# list_1.net
KiCad netlist of a schematic drawn in EAGLE
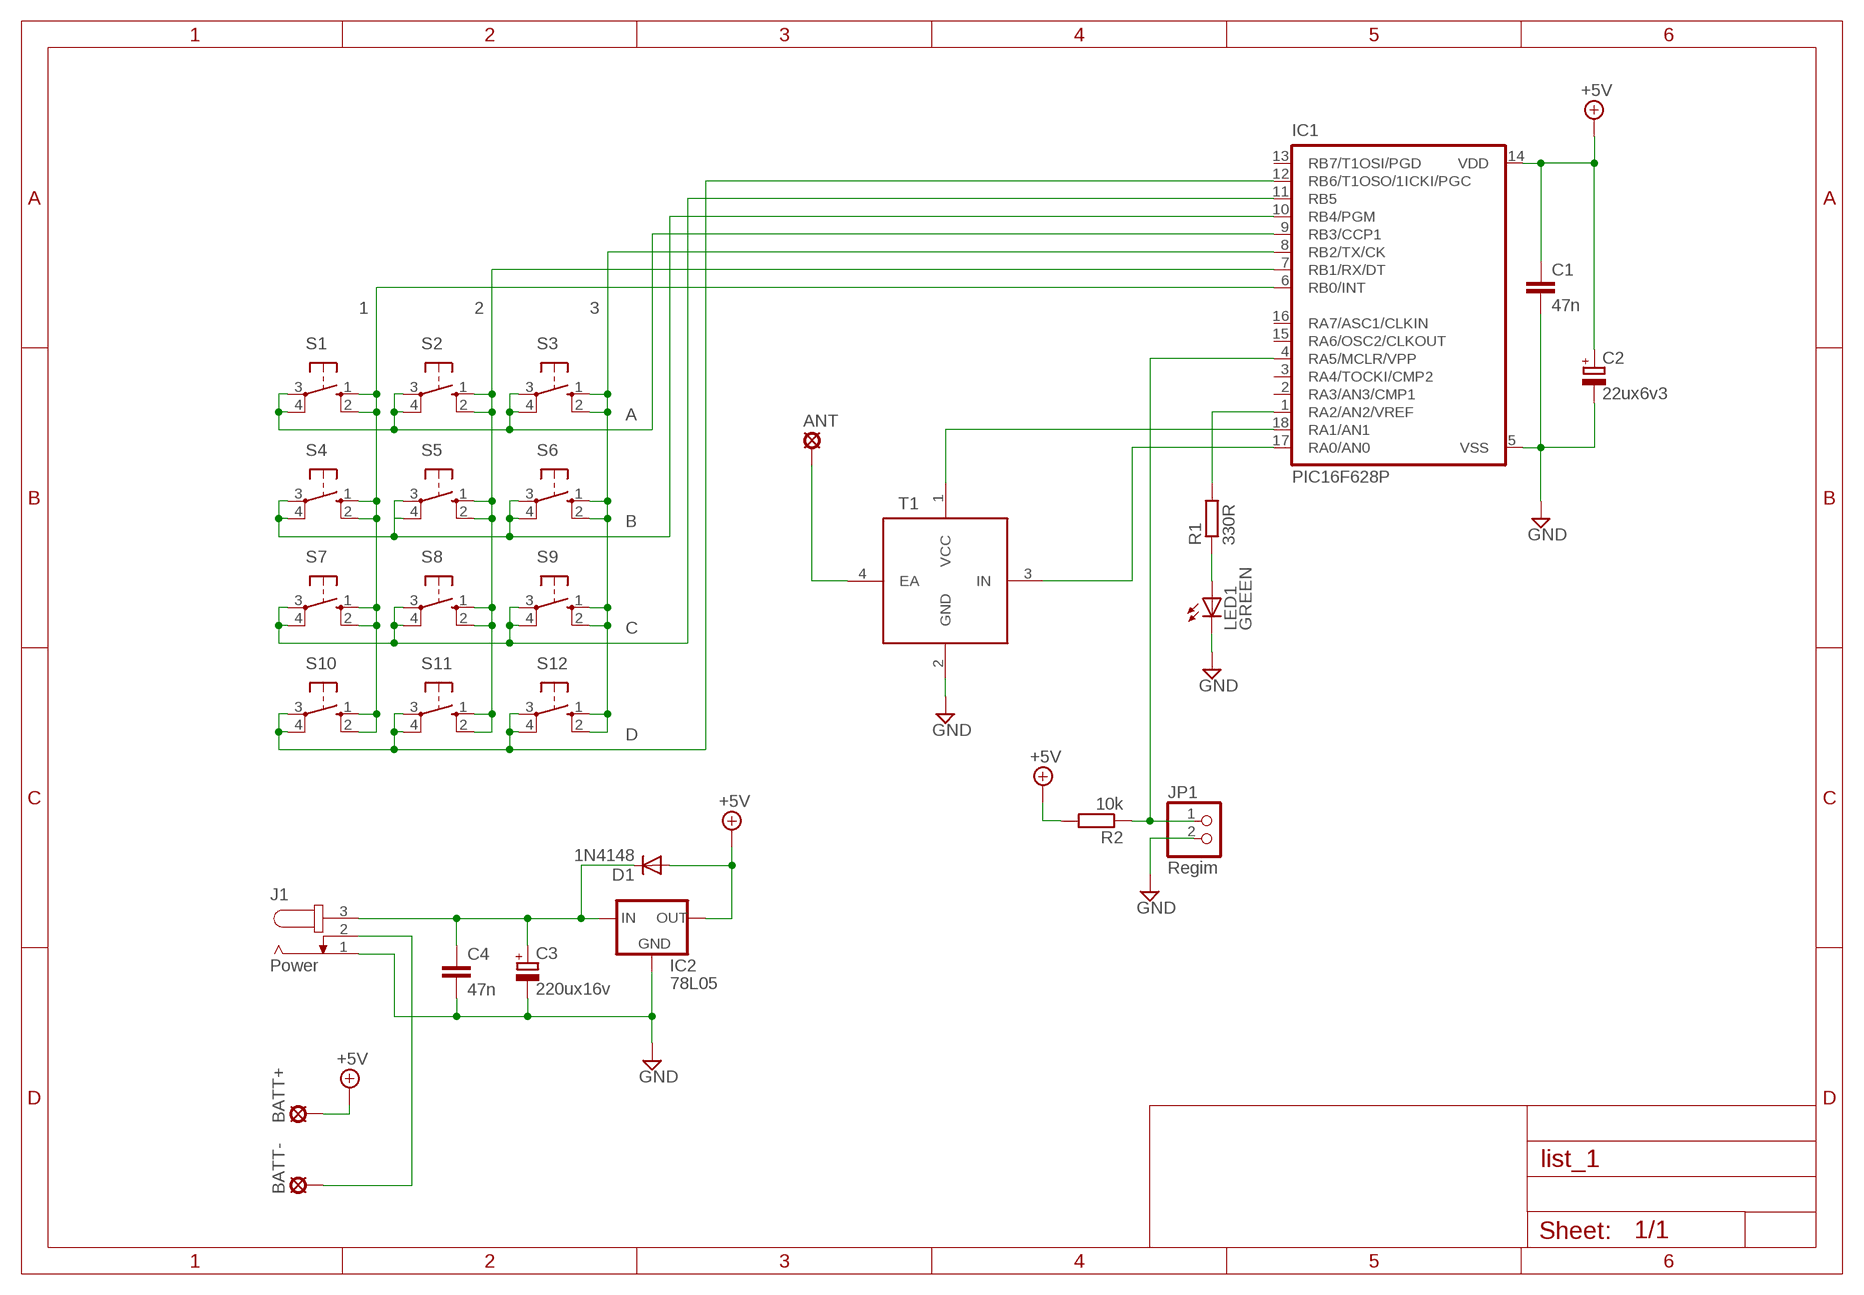
[diagram p0: schematic, sheet 1]

(export (version "E")
  (design (tool "Eeschema 10.0.6"))
  (components
    (comp (ref "ANT")
      (value "SE11")
      (footprint "eagle-import:SE11")
      (libsource (lib "eagle-import") (part "SE11"))
    )
    (comp (ref "BATT+")
      (value "SE11")
      (footprint "eagle-import:SE11")
      (libsource (lib "eagle-import") (part "SE11"))
    )
    (comp (ref "BATT-")
      (value "SE11")
      (footprint "eagle-import:SE11")
      (libsource (lib "eagle-import") (part "SE11"))
    )
    (comp (ref "C1")
      (value "47n")
      (footprint "eagle-import:C050-025X075")
      (libsource (lib "eagle-import") (part "C-EU050-025X075"))
    )
    (comp (ref "C2")
      (value "22ux6v3")
      (footprint "eagle-import:E2,5-5")
      (libsource (lib "eagle-import") (part "CPOL-EUE2.5-5"))
    )
    (comp (ref "C3")
      (value "220ux16v")
      (footprint "eagle-import:E2,5-5")
      (libsource (lib "eagle-import") (part "CPOL-EUE2.5-5"))
    )
    (comp (ref "C4")
      (value "47n")
      (footprint "eagle-import:C050-025X075")
      (libsource (lib "eagle-import") (part "C-EU050-025X075"))
    )
    (comp (ref "D1")
      (value "1N4148")
      (footprint "eagle-import:DO35-7")
      (libsource (lib "eagle-import") (part "1N4148DO35-7"))
    )
    (comp (ref "IC1")
      (value "PIC16F628P")
      (footprint "eagle-import:DIL18")
      (libsource (lib "eagle-import") (part "PIC16F628P"))
    )
    (comp (ref "IC2")
      (value "78L05")
      (footprint "eagle-import:78LXX")
      (libsource (lib "eagle-import") (part "78LXX"))
    )
    (comp (ref "J1")
      (value "Power")
      (footprint "eagle-import:SPC4077")
      (libsource (lib "eagle-import") (part "JACK-PLUG0"))
    )
    (comp (ref "JP1")
      (value "Regim")
      (footprint "eagle-import:1X02")
      (libsource (lib "eagle-import") (part "PINHD-1X2"))
    )
    (comp (ref "LED1")
      (value "GREEN")
      (footprint "eagle-import:LED3MM")
      (libsource (lib "eagle-import") (part "LED3MM"))
    )
    (comp (ref "R1")
      (value "330R")
      (footprint "eagle-import:0207_10")
      (libsource (lib "eagle-import") (part "R-EU_0207/10"))
    )
    (comp (ref "R2")
      (value "10k")
      (footprint "eagle-import:0207_10")
      (libsource (lib "eagle-import") (part "R-EU_0207/10"))
    )
    (comp (ref "S1")
      (value "40-XX")
      (footprint "eagle-import:B3F-40XX")
      (libsource (lib "eagle-import") (part "40-XX"))
    )
    (comp (ref "S2")
      (value "40-XX")
      (footprint "eagle-import:B3F-40XX")
      (libsource (lib "eagle-import") (part "40-XX"))
    )
    (comp (ref "S3")
      (value "40-XX")
      (footprint "eagle-import:B3F-40XX")
      (libsource (lib "eagle-import") (part "40-XX"))
    )
    (comp (ref "S4")
      (value "40-XX")
      (footprint "eagle-import:B3F-40XX")
      (libsource (lib "eagle-import") (part "40-XX"))
    )
    (comp (ref "S5")
      (value "40-XX")
      (footprint "eagle-import:B3F-40XX")
      (libsource (lib "eagle-import") (part "40-XX"))
    )
    (comp (ref "S6")
      (value "40-XX")
      (footprint "eagle-import:B3F-40XX")
      (libsource (lib "eagle-import") (part "40-XX"))
    )
    (comp (ref "S7")
      (value "40-XX")
      (footprint "eagle-import:B3F-40XX")
      (libsource (lib "eagle-import") (part "40-XX"))
    )
    (comp (ref "S8")
      (value "40-XX")
      (footprint "eagle-import:B3F-40XX")
      (libsource (lib "eagle-import") (part "40-XX"))
    )
    (comp (ref "S9")
      (value "40-XX")
      (footprint "eagle-import:B3F-40XX")
      (libsource (lib "eagle-import") (part "40-XX"))
    )
    (comp (ref "S10")
      (value "40-XX")
      (footprint "eagle-import:B3F-40XX")
      (libsource (lib "eagle-import") (part "40-XX"))
    )
    (comp (ref "S11")
      (value "40-XX")
      (footprint "eagle-import:B3F-40XX")
      (libsource (lib "eagle-import") (part "40-XX"))
    )
    (comp (ref "S12")
      (value "40-XX")
      (footprint "eagle-import:B3F-40XX")
      (libsource (lib "eagle-import") (part "40-XX"))
    )
    (comp (ref "T1")
      (value "RT4")
      (footprint "eagle-import:RT4")
      (libsource (lib "eagle-import") (part "RT4"))
    )
  )
  (nets
    (net (code "1") (name "+5V") (class "Default")
      (node (ref "BATT+") (pin "MP") (pinfunction "MP_MP") (pintype "passive"))
      (node (ref "C1") (pin "1") (pinfunction "1_1") (pintype "passive"))
      (node (ref "C2") (pin "+") (pinfunction "+_+") (pintype "passive"))
      (node (ref "D1") (pin "A") (pinfunction "A_A") (pintype "passive"))
      (node (ref "IC1") (pin "14") (pinfunction "VDD_14") (pintype "power_in"))
      (node (ref "IC2") (pin "OUT") (pinfunction "OUT_OUT") (pintype "passive"))
      (node (ref "R2") (pin "2") (pinfunction "2_2") (pintype "passive"))
    )
    (net (code "2") (name "GND") (class "Default")
      (node (ref "C1") (pin "2") (pinfunction "2_2") (pintype "passive"))
      (node (ref "C2") (pin "-") (pinfunction "-_-") (pintype "passive"))
      (node (ref "C3") (pin "-") (pinfunction "-_-") (pintype "passive"))
      (node (ref "C4") (pin "2") (pinfunction "2_2") (pintype "passive"))
      (node (ref "IC1") (pin "5") (pinfunction "VSS_5") (pintype "power_in"))
      (node (ref "IC2") (pin "GND") (pinfunction "GND_GND") (pintype "input"))
      (node (ref "J1") (pin "1") (pinfunction "1_1") (pintype "passive"))
      (node (ref "JP1") (pin "2") (pinfunction "2_2") (pintype "passive"))
      (node (ref "LED1") (pin "K") (pinfunction "C_K") (pintype "passive"))
      (node (ref "T1") (pin "2") (pinfunction "GND_2") (pintype "bidirectional"))
    )
    (net (code "3") (name "Net-(BATT--PadMP)") (class "Default")
      (node (ref "BATT-") (pin "MP") (pinfunction "MP_MP") (pintype "passive"))
      (node (ref "J1") (pin "2") (pinfunction "2_2") (pintype "passive"))
    )
    (net (code "4") (name "Net-(C3-Pad+)") (class "Default")
      (node (ref "C3") (pin "+") (pinfunction "+_+") (pintype "passive"))
      (node (ref "C4") (pin "1") (pinfunction "1_1") (pintype "passive"))
      (node (ref "D1") (pin "C") (pinfunction "C_C") (pintype "passive"))
      (node (ref "IC2") (pin "IN") (pinfunction "IN_IN") (pintype "input"))
      (node (ref "J1") (pin "3") (pinfunction "3_3") (pintype "passive"))
    )
    (net (code "5") (name "Net-(IC1-RA0{slash}AN0)") (class "Default")
      (node (ref "IC1") (pin "17") (pinfunction "RA0/AN0_17") (pintype "bidirectional"))
      (node (ref "T1") (pin "3") (pinfunction "IN_3") (pintype "bidirectional"))
    )
    (net (code "6") (name "Net-(IC1-RA1{slash}AN1)") (class "Default")
      (node (ref "IC1") (pin "18") (pinfunction "RA1/AN1_18") (pintype "bidirectional"))
      (node (ref "T1") (pin "1") (pinfunction "VCC_1") (pintype "bidirectional"))
    )
    (net (code "7") (name "Net-(IC1-RA2{slash}AN2{slash}VREF)") (class "Default")
      (node (ref "IC1") (pin "1") (pinfunction "RA2/AN2/VREF_1") (pintype "bidirectional"))
      (node (ref "R1") (pin "2") (pinfunction "2_2") (pintype "passive"))
    )
    (net (code "8") (name "Net-(IC1-RA5{slash}MCLR{slash}VPP)") (class "Default")
      (node (ref "IC1") (pin "4") (pinfunction "RA5/MCLR/VPP_4") (pintype "input"))
      (node (ref "JP1") (pin "1") (pinfunction "1_1") (pintype "passive"))
      (node (ref "R2") (pin "1") (pinfunction "1_1") (pintype "passive"))
    )
    (net (code "9") (name "Net-(IC1-RB0{slash}INT)") (class "Default")
      (node (ref "IC1") (pin "6") (pinfunction "RB0/INT_6") (pintype "bidirectional"))
      (node (ref "S1") (pin "1") (pinfunction "S_1") (pintype "passive"))
      (node (ref "S1") (pin "2") (pinfunction "S1_2") (pintype "passive"))
      (node (ref "S10") (pin "1") (pinfunction "S_1") (pintype "passive"))
      (node (ref "S10") (pin "2") (pinfunction "S1_2") (pintype "passive"))
      (node (ref "S4") (pin "1") (pinfunction "S_1") (pintype "passive"))
      (node (ref "S4") (pin "2") (pinfunction "S1_2") (pintype "passive"))
      (node (ref "S7") (pin "1") (pinfunction "S_1") (pintype "passive"))
      (node (ref "S7") (pin "2") (pinfunction "S1_2") (pintype "passive"))
    )
    (net (code "10") (name "Net-(IC1-RB1{slash}RX{slash}DT)") (class "Default")
      (node (ref "IC1") (pin "7") (pinfunction "RB1/RX/DT_7") (pintype "bidirectional"))
      (node (ref "S11") (pin "1") (pinfunction "S_1") (pintype "passive"))
      (node (ref "S11") (pin "2") (pinfunction "S1_2") (pintype "passive"))
      (node (ref "S2") (pin "1") (pinfunction "S_1") (pintype "passive"))
      (node (ref "S2") (pin "2") (pinfunction "S1_2") (pintype "passive"))
      (node (ref "S5") (pin "1") (pinfunction "S_1") (pintype "passive"))
      (node (ref "S5") (pin "2") (pinfunction "S1_2") (pintype "passive"))
      (node (ref "S8") (pin "1") (pinfunction "S_1") (pintype "passive"))
      (node (ref "S8") (pin "2") (pinfunction "S1_2") (pintype "passive"))
    )
    (net (code "11") (name "Net-(IC1-RB2{slash}TX{slash}CK)") (class "Default")
      (node (ref "IC1") (pin "8") (pinfunction "RB2/TX/CK_8") (pintype "bidirectional"))
      (node (ref "S12") (pin "1") (pinfunction "S_1") (pintype "passive"))
      (node (ref "S12") (pin "2") (pinfunction "S1_2") (pintype "passive"))
      (node (ref "S3") (pin "1") (pinfunction "S_1") (pintype "passive"))
      (node (ref "S3") (pin "2") (pinfunction "S1_2") (pintype "passive"))
      (node (ref "S6") (pin "1") (pinfunction "S_1") (pintype "passive"))
      (node (ref "S6") (pin "2") (pinfunction "S1_2") (pintype "passive"))
      (node (ref "S9") (pin "1") (pinfunction "S_1") (pintype "passive"))
      (node (ref "S9") (pin "2") (pinfunction "S1_2") (pintype "passive"))
    )
    (net (code "12") (name "Net-(IC1-RB3{slash}CCP1)") (class "Default")
      (node (ref "IC1") (pin "9") (pinfunction "RB3/CCP1_9") (pintype "bidirectional"))
      (node (ref "S1") (pin "3") (pinfunction "P_3") (pintype "passive"))
      (node (ref "S1") (pin "4") (pinfunction "P1_4") (pintype "passive"))
      (node (ref "S2") (pin "3") (pinfunction "P_3") (pintype "passive"))
      (node (ref "S2") (pin "4") (pinfunction "P1_4") (pintype "passive"))
      (node (ref "S3") (pin "3") (pinfunction "P_3") (pintype "passive"))
      (node (ref "S3") (pin "4") (pinfunction "P1_4") (pintype "passive"))
    )
    (net (code "13") (name "Net-(IC1-RB4{slash}PGM)") (class "Default")
      (node (ref "IC1") (pin "10") (pinfunction "RB4/PGM_10") (pintype "bidirectional"))
      (node (ref "S4") (pin "3") (pinfunction "P_3") (pintype "passive"))
      (node (ref "S4") (pin "4") (pinfunction "P1_4") (pintype "passive"))
      (node (ref "S5") (pin "3") (pinfunction "P_3") (pintype "passive"))
      (node (ref "S5") (pin "4") (pinfunction "P1_4") (pintype "passive"))
      (node (ref "S6") (pin "3") (pinfunction "P_3") (pintype "passive"))
      (node (ref "S6") (pin "4") (pinfunction "P1_4") (pintype "passive"))
    )
    (net (code "14") (name "Net-(IC1-RB5)") (class "Default")
      (node (ref "IC1") (pin "11") (pinfunction "RB5_11") (pintype "bidirectional"))
      (node (ref "S7") (pin "3") (pinfunction "P_3") (pintype "passive"))
      (node (ref "S7") (pin "4") (pinfunction "P1_4") (pintype "passive"))
      (node (ref "S8") (pin "3") (pinfunction "P_3") (pintype "passive"))
      (node (ref "S8") (pin "4") (pinfunction "P1_4") (pintype "passive"))
      (node (ref "S9") (pin "3") (pinfunction "P_3") (pintype "passive"))
      (node (ref "S9") (pin "4") (pinfunction "P1_4") (pintype "passive"))
    )
    (net (code "15") (name "Net-(IC1-RB6{slash}T1OSO{slash}1ICKI{slash}PGC)") (class "Default")
      (node (ref "IC1") (pin "12") (pinfunction "RB6/T1OSO/1ICKI/PGC_12") (pintype "bidirectional"))
      (node (ref "S10") (pin "3") (pinfunction "P_3") (pintype "passive"))
      (node (ref "S10") (pin "4") (pinfunction "P1_4") (pintype "passive"))
      (node (ref "S11") (pin "3") (pinfunction "P_3") (pintype "passive"))
      (node (ref "S11") (pin "4") (pinfunction "P1_4") (pintype "passive"))
      (node (ref "S12") (pin "3") (pinfunction "P_3") (pintype "passive"))
      (node (ref "S12") (pin "4") (pinfunction "P1_4") (pintype "passive"))
    )
    (net (code "16") (name "Net-(LED1-PadA)") (class "Default")
      (node (ref "LED1") (pin "A") (pinfunction "A_A") (pintype "passive"))
      (node (ref "R1") (pin "1") (pinfunction "1_1") (pintype "passive"))
    )
    (net (code "17") (name "Net-(T1-EA)") (class "Default")
      (node (ref "ANT") (pin "MP") (pinfunction "MP_MP") (pintype "passive"))
      (node (ref "T1") (pin "4") (pinfunction "EA_4") (pintype "bidirectional"))
    )
    (net (code "18") (name "unconnected-(IC1-RA3{slash}AN3{slash}CMP1-Pad2)") (class "Default")
      (node (ref "IC1") (pin "2") (pinfunction "RA3/AN3/CMP1_2") (pintype "bidirectional"))
    )
    (net (code "19") (name "unconnected-(IC1-RA4{slash}TOCKI{slash}CMP2-Pad3)") (class "Default")
      (node (ref "IC1") (pin "3") (pinfunction "RA4/TOCKI/CMP2_3") (pintype "bidirectional"))
    )
    (net (code "20") (name "unconnected-(IC1-RA6{slash}OSC2{slash}CLKOUT-Pad15)") (class "Default")
      (node (ref "IC1") (pin "15") (pinfunction "RA6/OSC2/CLKOUT_15") (pintype "bidirectional"))
    )
    (net (code "21") (name "unconnected-(IC1-RA7{slash}ASC1{slash}CLKIN-Pad16)") (class "Default")
      (node (ref "IC1") (pin "16") (pinfunction "RA7/ASC1/CLKIN_16") (pintype "bidirectional"))
    )
    (net (code "22") (name "unconnected-(IC1-RB7{slash}T1OSI{slash}PGD-Pad13)") (class "Default")
      (node (ref "IC1") (pin "13") (pinfunction "RB7/T1OSI/PGD_13") (pintype "bidirectional"))
    )
  )
)
